# Connectors.net
KiCad netlist of a schematic drawn in Altium Designer
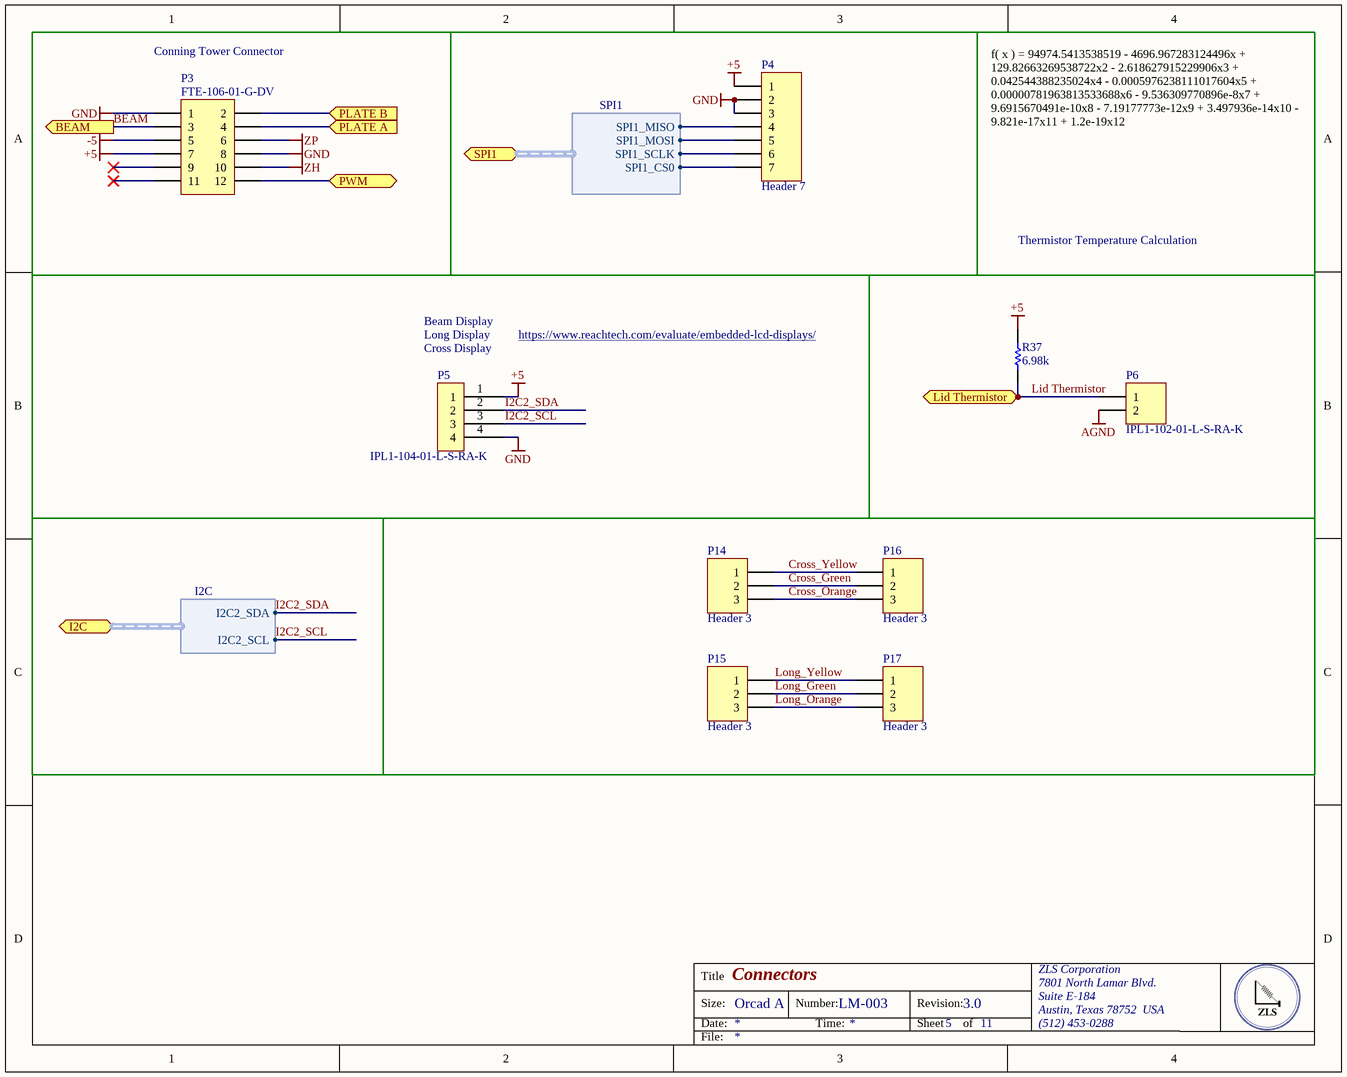
[diagram p0: Connectors.SchDoc]

(export (version "E")
  (design (tool "Eeschema 10.0.6"))
  (components
    (comp (ref "P3")
      (value "FTE-106-01-G-DV")
      (footprint "FTSH-106-01")
      (description "Header, 6-Pin, Dual row")
      (fields (field (name "MANUFACTURER") "Samtec") (field (name "PUBLISHER") "Altium Limited"))
      (libsource (lib "Conning Tower Adapter") (part "Header 6X2"))
    )
    (comp (ref "P4")
      (value "Header 7")
      (footprint "HDR1X7")
      (description "Header, 7-Pin")
      (fields (field (name "PUBLISHER") "Altium Limited"))
      (libsource (lib "Miscellaneous Connectors") (part "Header 7"))
    )
    (comp (ref "P5")
      (value "IPL1-104-01-L-S-RA-K")
      (footprint "IPL1-104-01")
      (description ".100 TERMINAL ASSY")
      (libsource (lib "ZLS_LIB") (part "53047-0410"))
    )
    (comp (ref "P6")
      (value "IPL1-102-01-L-S-RA-K")
      (footprint "IPL1-102-01")
      (description "CONN SHROUDED PWR HEADER 2POS")
      (libsource (lib "Miscellaneous Connectors") (part "Header 2H"))
    )
    (comp (ref "P14")
      (value "Header 3")
      (footprint "HDR1X3")
      (description "Header, 3-Pin")
      (fields (field (name "PUBLISHER") "Altium Limited"))
      (libsource (lib "") (part "Header 3_1"))
    )
    (comp (ref "P15")
      (value "Header 3")
      (footprint "HDR1X3")
      (description "Header, 3-Pin")
      (fields (field (name "PUBLISHER") "Altium Limited"))
      (libsource (lib "") (part "Header 3_1"))
    )
    (comp (ref "P16")
      (value "Header 3")
      (footprint "TLW-103-01-G-S-RA")
      (description "Header, 3-Pin")
      (fields (field (name "PUBLISHER") "Altium Limited"))
      (libsource (lib "Miscellaneous Connectors") (part "Header 3"))
    )
    (comp (ref "P17")
      (value "Header 3")
      (footprint "TLW-103-01-G-S-RA")
      (description "Header, 3-Pin")
      (fields (field (name "PUBLISHER") "Altium Limited"))
      (libsource (lib "Miscellaneous Connectors") (part "Header 3"))
    )
    (comp (ref "R37")
      (value "6K98 1% 0805(2012)")
      (footprint "RESC0805(2012)_N")
      (description "6K98 0.125W 1% 0805 (2012 Metric)  SMD")
      (fields
        (field (name "MANUFACTURER") "Vishay Dale")
        (field (name "MANUFACTURER PART NUMBER") "CRCW08056K98FKEA")
        (field (name "RESISTANCE (OHMS)") "6.98k")
      )
      (libsource (lib "Altium Content Vault") (part "CMP-1013-00606-1"))
    )
  )
  (nets
    (net (code "3") (name "+5") (class "Default")
      (node (ref "P3") (pin "7") (pinfunction "7_7") (pintype "passive"))
      (node (ref "P4") (pin "1") (pinfunction "1_1") (pintype "passive"))
      (node (ref "P5") (pin "1") (pinfunction "1_1") (pintype "passive"))
      (node (ref "R37") (pin "2") (pinfunction "2_2") (pintype "passive"))
    )
    (net (code "4") (name "-5") (class "Default")
      (node (ref "P3") (pin "5") (pinfunction "5_5") (pintype "passive"))
    )
    (net (code "5") (name "/BEAM") (class "Default")
      (node (ref "P3") (pin "3") (pinfunction "3_3") (pintype "passive"))
    )
    (net (code "6") (name "/Cross_Green") (class "Default")
      (node (ref "P14") (pin "2") (pinfunction "2_2") (pintype "passive"))
      (node (ref "P16") (pin "2") (pinfunction "2_2") (pintype "passive"))
    )
    (net (code "7") (name "/Cross_Orange") (class "Default")
      (node (ref "P14") (pin "3") (pinfunction "3_3") (pintype "passive"))
      (node (ref "P16") (pin "3") (pinfunction "3_3") (pintype "passive"))
    )
    (net (code "8") (name "/Cross_Yellow") (class "Default")
      (node (ref "P14") (pin "1") (pinfunction "1_1") (pintype "passive"))
      (node (ref "P16") (pin "1") (pinfunction "1_1") (pintype "passive"))
    )
    (net (code "9") (name "/I2C2_SCL") (class "Default")
      (node (ref "P5") (pin "3") (pinfunction "3_3") (pintype "passive"))
    )
    (net (code "10") (name "/I2C2_SDA") (class "Default")
      (node (ref "P5") (pin "2") (pinfunction "2_2") (pintype "passive"))
    )
    (net (code "11") (name "/Lid Thermistor") (class "Default")
      (node (ref "P6") (pin "1") (pinfunction "1_1") (pintype "passive"))
      (node (ref "R37") (pin "1") (pinfunction "1_1") (pintype "passive"))
    )
    (net (code "12") (name "/Long_Green") (class "Default")
      (node (ref "P15") (pin "2") (pinfunction "2_2") (pintype "passive"))
      (node (ref "P17") (pin "2") (pinfunction "2_2") (pintype "passive"))
    )
    (net (code "13") (name "/Long_Orange") (class "Default")
      (node (ref "P15") (pin "3") (pinfunction "3_3") (pintype "passive"))
      (node (ref "P17") (pin "3") (pinfunction "3_3") (pintype "passive"))
    )
    (net (code "14") (name "/Long_Yellow") (class "Default")
      (node (ref "P15") (pin "1") (pinfunction "1_1") (pintype "passive"))
      (node (ref "P17") (pin "1") (pinfunction "1_1") (pintype "passive"))
    )
    (net (code "15") (name "/PLATE A") (class "Default")
      (node (ref "P3") (pin "4") (pinfunction "4_4") (pintype "passive"))
    )
    (net (code "16") (name "/PLATE B") (class "Default")
      (node (ref "P3") (pin "2") (pinfunction "2_2") (pintype "passive"))
    )
    (net (code "17") (name "/PWM") (class "Default")
      (node (ref "P3") (pin "12") (pinfunction "12_12") (pintype "passive"))
    )
    (net (code "18") (name "/SPI1_CS0") (class "Default")
      (node (ref "P4") (pin "7") (pinfunction "7_7") (pintype "passive"))
    )
    (net (code "19") (name "/SPI1_MISO") (class "Default")
      (node (ref "P4") (pin "4") (pinfunction "4_4") (pintype "passive"))
    )
    (net (code "20") (name "/SPI1_MOSI") (class "Default")
      (node (ref "P4") (pin "5") (pinfunction "5_5") (pintype "passive"))
    )
    (net (code "21") (name "/SPI1_SCLK") (class "Default")
      (node (ref "P4") (pin "6") (pinfunction "6_6") (pintype "passive"))
    )
    (net (code "24") (name "AGND") (class "Default")
      (node (ref "P6") (pin "2") (pinfunction "2_2") (pintype "passive"))
    )
    (net (code "25") (name "GND") (class "Default")
      (node (ref "P3") (pin "1") (pinfunction "1_1") (pintype "passive"))
      (node (ref "P3") (pin "8") (pinfunction "8_8") (pintype "passive"))
      (node (ref "P4") (pin "2") (pinfunction "2_2") (pintype "passive"))
      (node (ref "P4") (pin "3") (pinfunction "3_3") (pintype "passive"))
      (node (ref "P5") (pin "4") (pinfunction "4_4") (pintype "passive"))
    )
    (net (code "26") (name "ZH") (class "Default")
      (node (ref "P3") (pin "10") (pinfunction "10_10") (pintype "passive"))
    )
    (net (code "27") (name "ZP") (class "Default")
      (node (ref "P3") (pin "6") (pinfunction "6_6") (pintype "passive"))
    )
    (net (code "28") (name "unconnected-(P3-Pad9)") (class "Default")
      (node (ref "P3") (pin "9") (pinfunction "9_9") (pintype "passive+no_connect"))
    )
    (net (code "29") (name "unconnected-(P3-Pad11)") (class "Default")
      (node (ref "P3") (pin "11") (pinfunction "11_11") (pintype "passive+no_connect"))
    )
  )
)
